# POE_PD_2_P-Schalter.net
KiCad netlist of a schematic drawn in EAGLE
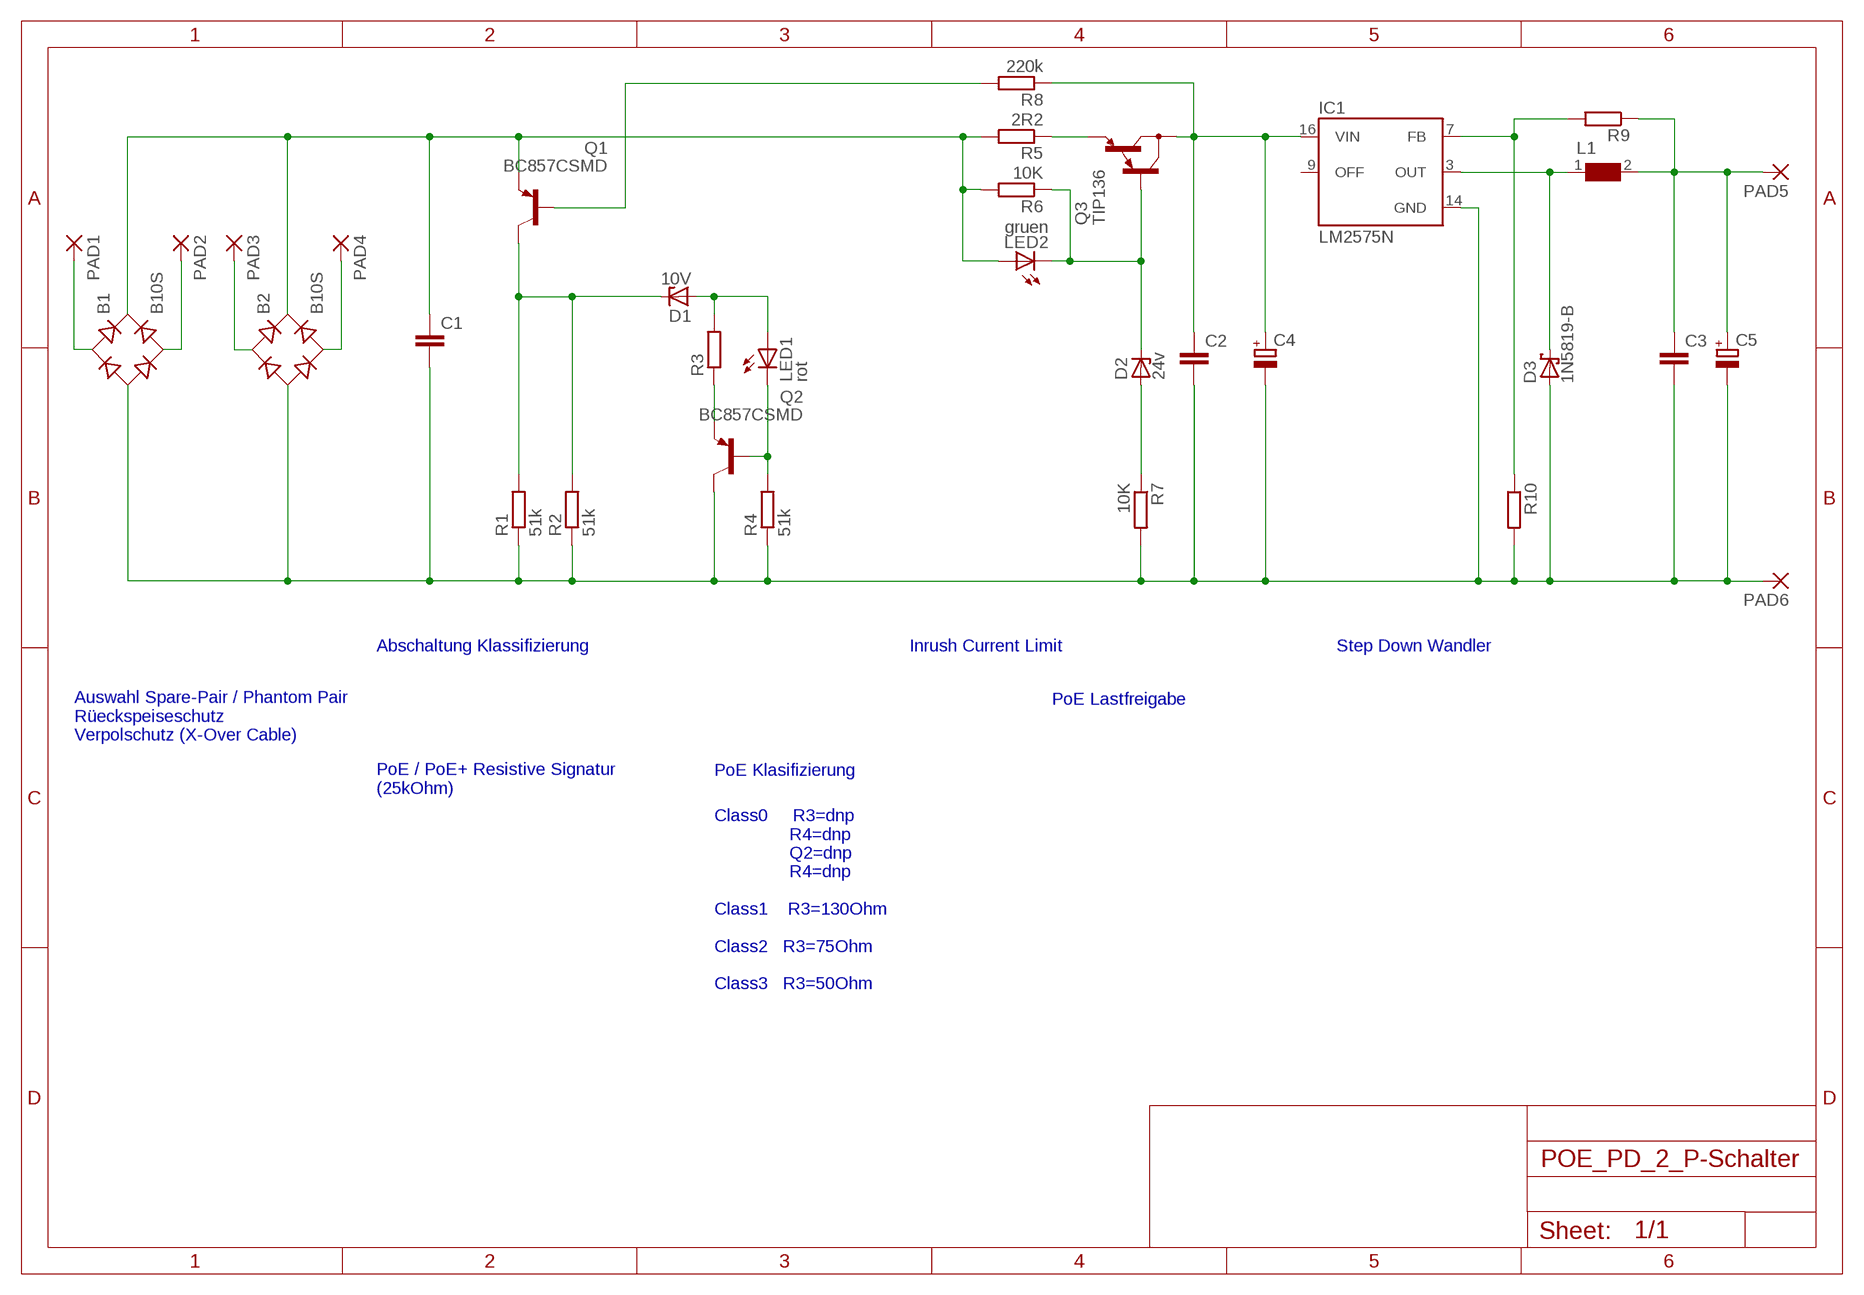
[diagram p0: schematic, sheet 1]

(export (version "E")
  (design (tool "Eeschema 10.0.6"))
  (components
    (comp (ref "B1")
      (value "B10S")
      (footprint "eagle-import:MBS")
      (libsource (lib "eagle-import") (part "BS10"))
    )
    (comp (ref "B2")
      (value "B10S")
      (footprint "eagle-import:MBS")
      (libsource (lib "eagle-import") (part "BS10"))
    )
    (comp (ref "C1")
      (value "C-EUC0805")
      (footprint "eagle-import:C0805")
      (libsource (lib "eagle-import") (part "C-EUC0805"))
    )
    (comp (ref "C2")
      (value "C-EUC0805")
      (footprint "eagle-import:C0805")
      (libsource (lib "eagle-import") (part "C-EUC0805"))
    )
    (comp (ref "C3")
      (value "C-EUC0805")
      (footprint "eagle-import:C0805")
      (libsource (lib "eagle-import") (part "C-EUC0805"))
    )
    (comp (ref "C4")
      (value "CPOL-EU153CLV-0807")
      (footprint "eagle-import:153CLV-0807")
      (libsource (lib "eagle-import") (part "CPOL-EU153CLV-0807"))
    )
    (comp (ref "C5")
      (value "CPOL-EU153CLV-0807")
      (footprint "eagle-import:153CLV-0807")
      (libsource (lib "eagle-import") (part "CPOL-EU153CLV-0807"))
    )
    (comp (ref "D1")
      (value "10V")
      (footprint "eagle-import:SOT23")
      (libsource (lib "eagle-import") (part "ZENER-DIODESOT23"))
    )
    (comp (ref "D2")
      (value "24v")
      (footprint "eagle-import:SOT23")
      (libsource (lib "eagle-import") (part "ZENER-DIODESOT23"))
    )
    (comp (ref "D3")
      (value "1N5819-B")
      (footprint "eagle-import:DO41-7.6")
      (libsource (lib "eagle-import") (part "1N5819-B"))
    )
    (comp (ref "IC1")
      (value "LM2575N")
      (footprint "eagle-import:DIL16")
      (libsource (lib "eagle-import") (part "LM2575N"))
    )
    (comp (ref "L1")
      (value "WE-PD2_S")
      (footprint "eagle-import:WE-PD2_S")
      (libsource (lib "eagle-import") (part "WE-PD2_S"))
    )
    (comp (ref "LED1")
      (value "rot")
      (footprint "eagle-import:CHIP-LED0805")
      (libsource (lib "eagle-import") (part "LEDCHIP-LED0805"))
    )
    (comp (ref "LED2")
      (value "gruen")
      (footprint "eagle-import:CHIP-LED0805")
      (libsource (lib "eagle-import") (part "LEDCHIP-LED0805"))
    )
    (comp (ref "PAD1")
      (value "2,15/1,0")
      (footprint "eagle-import:2,15_1,0")
      (libsource (lib "eagle-import") (part "2,15/1,0"))
    )
    (comp (ref "PAD2")
      (value "2,15/1,0")
      (footprint "eagle-import:2,15_1,0")
      (libsource (lib "eagle-import") (part "2,15/1,0"))
    )
    (comp (ref "PAD3")
      (value "2,15/1,0")
      (footprint "eagle-import:2,15_1,0")
      (libsource (lib "eagle-import") (part "2,15/1,0"))
    )
    (comp (ref "PAD4")
      (value "2,15/1,0")
      (footprint "eagle-import:2,15_1,0")
      (libsource (lib "eagle-import") (part "2,15/1,0"))
    )
    (comp (ref "PAD5")
      (value "2,15/1,0")
      (footprint "eagle-import:2,15_1,0")
      (libsource (lib "eagle-import") (part "2,15/1,0"))
    )
    (comp (ref "PAD6")
      (value "2,15/1,0")
      (footprint "eagle-import:2,15_1,0")
      (libsource (lib "eagle-import") (part "2,15/1,0"))
    )
    (comp (ref "Q1")
      (value "BC857CSMD")
      (footprint "eagle-import:SOT23-BEC")
      (libsource (lib "eagle-import") (part "BC857SMDC"))
    )
    (comp (ref "Q2")
      (value "BC857CSMD")
      (footprint "eagle-import:SOT23-BEC")
      (libsource (lib "eagle-import") (part "BC857SMDC"))
    )
    (comp (ref "Q3")
      (value "TIP136")
      (footprint "eagle-import:TO220")
      (libsource (lib "eagle-import") (part "TIP136"))
    )
    (comp (ref "R1")
      (value "51k")
      (footprint "eagle-import:R0603")
      (libsource (lib "eagle-import") (part "R-EU_R0603"))
    )
    (comp (ref "R2")
      (value "51k")
      (footprint "eagle-import:R0603")
      (libsource (lib "eagle-import") (part "R-EU_R0603"))
    )
    (comp (ref "R3")
      (value "R-EU_R0603")
      (footprint "eagle-import:R0603")
      (libsource (lib "eagle-import") (part "R-EU_R0603"))
    )
    (comp (ref "R4")
      (value "51k")
      (footprint "eagle-import:R0603")
      (libsource (lib "eagle-import") (part "R-EU_R0603"))
    )
    (comp (ref "R5")
      (value "2R2")
      (footprint "eagle-import:R0603")
      (libsource (lib "eagle-import") (part "R-EU_R0603"))
    )
    (comp (ref "R6")
      (value "10K")
      (footprint "eagle-import:R0603")
      (libsource (lib "eagle-import") (part "R-EU_R0603"))
    )
    (comp (ref "R7")
      (value "10K")
      (footprint "eagle-import:R0603")
      (libsource (lib "eagle-import") (part "R-EU_R0603"))
    )
    (comp (ref "R8")
      (value "220k")
      (footprint "eagle-import:R0603")
      (libsource (lib "eagle-import") (part "R-EU_R0603"))
    )
    (comp (ref "R9")
      (value "R-EU_R0603")
      (footprint "eagle-import:R0603")
      (libsource (lib "eagle-import") (part "R-EU_R0603"))
    )
    (comp (ref "R10")
      (value "R-EU_R0603")
      (footprint "eagle-import:R0603")
      (libsource (lib "eagle-import") (part "R-EU_R0603"))
    )
  )
  (nets
    (net (code "1") (name "Net-(B1-Pad+)") (class "Default")
      (node (ref "B1") (pin "+") (pinfunction "+_+") (pintype "passive"))
      (node (ref "B2") (pin "+") (pinfunction "+_+") (pintype "passive"))
      (node (ref "C1") (pin "1") (pinfunction "1_1") (pintype "passive"))
      (node (ref "LED2") (pin "A") (pinfunction "A_A") (pintype "passive"))
      (node (ref "Q1") (pin "E") (pinfunction "E_E") (pintype "passive"))
      (node (ref "R5") (pin "2") (pinfunction "2_2") (pintype "passive"))
      (node (ref "R6") (pin "2") (pinfunction "2_2") (pintype "passive"))
    )
    (net (code "2") (name "Net-(D1-A)") (class "Default")
      (node (ref "D1") (pin "1") (pinfunction "A_1") (pintype "passive"))
      (node (ref "LED1") (pin "A") (pinfunction "A_A") (pintype "passive"))
      (node (ref "R3") (pin "2") (pinfunction "2_2") (pintype "passive"))
    )
    (net (code "3") (name "Net-(D1-C)") (class "Default")
      (node (ref "D1") (pin "3") (pinfunction "C_3") (pintype "passive"))
      (node (ref "Q1") (pin "C") (pinfunction "C_C") (pintype "passive"))
      (node (ref "R1") (pin "2") (pinfunction "2_2") (pintype "passive"))
      (node (ref "R2") (pin "2") (pinfunction "2_2") (pintype "passive"))
    )
    (net (code "4") (name "Net-(D2-A)") (class "Default")
      (node (ref "D2") (pin "1") (pinfunction "A_1") (pintype "passive"))
      (node (ref "R7") (pin "1") (pinfunction "1_1") (pintype "passive"))
    )
    (net (code "5") (name "Net-(D2-C)") (class "Default")
      (node (ref "D2") (pin "3") (pinfunction "C_3") (pintype "passive"))
      (node (ref "LED2") (pin "C") (pinfunction "C_C") (pintype "passive"))
      (node (ref "Q3") (pin "1") (pinfunction "B_1") (pintype "passive"))
      (node (ref "R6") (pin "1") (pinfunction "1_1") (pintype "passive"))
    )
    (net (code "6") (name "Net-(IC1-FB)") (class "Default")
      (node (ref "IC1") (pin "7") (pinfunction "FB_7") (pintype "input"))
      (node (ref "R10") (pin "1") (pinfunction "1_1") (pintype "passive"))
      (node (ref "R9") (pin "2") (pinfunction "2_2") (pintype "passive"))
    )
    (net (code "7") (name "Net-(IC1-GND)") (class "Default")
      (node (ref "B1") (pin "-") (pinfunction "-_-") (pintype "passive"))
      (node (ref "B2") (pin "-") (pinfunction "-_-") (pintype "passive"))
      (node (ref "C1") (pin "2") (pinfunction "2_2") (pintype "passive"))
      (node (ref "C2") (pin "2") (pinfunction "2_2") (pintype "passive"))
      (node (ref "C3") (pin "2") (pinfunction "2_2") (pintype "passive"))
      (node (ref "C4") (pin "-") (pinfunction "-_-") (pintype "passive"))
      (node (ref "C5") (pin "-") (pinfunction "-_-") (pintype "passive"))
      (node (ref "D3") (pin "A") (pinfunction "A_A") (pintype "passive"))
      (node (ref "IC1") (pin "14") (pinfunction "GND_14") (pintype "power_in"))
      (node (ref "PAD6") (pin "1") (pinfunction "P_1") (pintype "passive"))
      (node (ref "Q2") (pin "C") (pinfunction "C_C") (pintype "passive"))
      (node (ref "R1") (pin "1") (pinfunction "1_1") (pintype "passive"))
      (node (ref "R10") (pin "2") (pinfunction "2_2") (pintype "passive"))
      (node (ref "R2") (pin "1") (pinfunction "1_1") (pintype "passive"))
      (node (ref "R4") (pin "1") (pinfunction "1_1") (pintype "passive"))
      (node (ref "R7") (pin "2") (pinfunction "2_2") (pintype "passive"))
    )
    (net (code "8") (name "Net-(IC1-OUT)") (class "Default")
      (node (ref "D3") (pin "C") (pinfunction "C_C") (pintype "passive"))
      (node (ref "IC1") (pin "3") (pinfunction "OUT_3") (pintype "output"))
      (node (ref "L1") (pin "1") (pinfunction "1_1") (pintype "passive"))
    )
    (net (code "9") (name "Net-(IC1-VIN)") (class "Default")
      (node (ref "C2") (pin "1") (pinfunction "1_1") (pintype "passive"))
      (node (ref "C4") (pin "+") (pinfunction "+_+") (pintype "passive"))
      (node (ref "IC1") (pin "16") (pinfunction "VIN_16") (pintype "power_in"))
      (node (ref "Q3") (pin "2") (pinfunction "C_2") (pintype "passive"))
      (node (ref "R8") (pin "1") (pinfunction "1_1") (pintype "passive"))
    )
    (net (code "10") (name "Net-(LED1-PadC)") (class "Default")
      (node (ref "LED1") (pin "C") (pinfunction "C_C") (pintype "passive"))
      (node (ref "Q2") (pin "B") (pinfunction "B_B") (pintype "passive"))
      (node (ref "R4") (pin "2") (pinfunction "2_2") (pintype "passive"))
    )
    (net (code "11") (name "Net-(PAD1-P)") (class "Default")
      (node (ref "B1") (pin "AC1") (pinfunction "AC1_AC1") (pintype "passive"))
      (node (ref "PAD1") (pin "1") (pinfunction "P_1") (pintype "passive"))
    )
    (net (code "12") (name "Net-(PAD2-P)") (class "Default")
      (node (ref "B1") (pin "AC2") (pinfunction "AC2_AC2") (pintype "passive"))
      (node (ref "PAD2") (pin "1") (pinfunction "P_1") (pintype "passive"))
    )
    (net (code "13") (name "Net-(PAD3-P)") (class "Default")
      (node (ref "B2") (pin "AC1") (pinfunction "AC1_AC1") (pintype "passive"))
      (node (ref "PAD3") (pin "1") (pinfunction "P_1") (pintype "passive"))
    )
    (net (code "14") (name "Net-(PAD4-P)") (class "Default")
      (node (ref "B2") (pin "AC2") (pinfunction "AC2_AC2") (pintype "passive"))
      (node (ref "PAD4") (pin "1") (pinfunction "P_1") (pintype "passive"))
    )
    (net (code "15") (name "Net-(PAD5-P)") (class "Default")
      (node (ref "C3") (pin "1") (pinfunction "1_1") (pintype "passive"))
      (node (ref "C5") (pin "+") (pinfunction "+_+") (pintype "passive"))
      (node (ref "L1") (pin "2") (pinfunction "2_2") (pintype "passive"))
      (node (ref "PAD5") (pin "1") (pinfunction "P_1") (pintype "passive"))
      (node (ref "R9") (pin "1") (pinfunction "1_1") (pintype "passive"))
    )
    (net (code "16") (name "Net-(Q1-PadB)") (class "Default")
      (node (ref "Q1") (pin "B") (pinfunction "B_B") (pintype "passive"))
      (node (ref "R8") (pin "2") (pinfunction "2_2") (pintype "passive"))
    )
    (net (code "17") (name "Net-(Q2-PadE)") (class "Default")
      (node (ref "Q2") (pin "E") (pinfunction "E_E") (pintype "passive"))
      (node (ref "R3") (pin "1") (pinfunction "1_1") (pintype "passive"))
    )
    (net (code "18") (name "Net-(Q3-E)") (class "Default")
      (node (ref "Q3") (pin "3") (pinfunction "E_3") (pintype "passive"))
      (node (ref "R5") (pin "1") (pinfunction "1_1") (pintype "passive"))
    )
    (net (code "19") (name "unconnected-(IC1-OFF-Pad9)") (class "Default")
      (node (ref "IC1") (pin "9") (pinfunction "OFF_9") (pintype "input"))
    )
  )
)
